# isoSPI-transceiver.net
KiCad netlist of a schematic drawn in Altium Designer
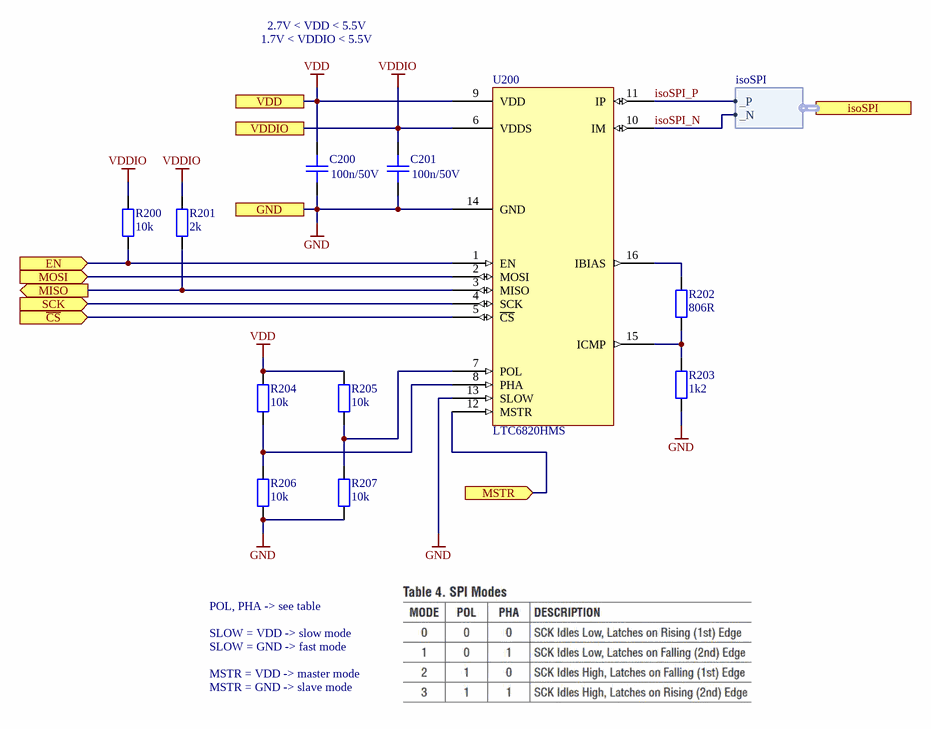
[diagram p0: isoSPI-transceiver.SchDoc]

(export (version "E")
  (design (tool "Eeschema 10.0.6"))
  (components
    (comp (ref "C200")
      (value "100n/50V")
      (footprint "CAPC1608X08N")
      (description "MLCC")
      (fields (field (name "PART NUMBER") "gen_C_ceramic_100n_50V_X7R_0603"))
      (libsource (lib "OE750") (part "C"))
    )
    (comp (ref "C201")
      (value "100n/50V")
      (footprint "CAPC1608X08N")
      (description "MLCC")
      (fields (field (name "PART NUMBER") "gen_C_ceramic_100n_50V_X7R_0603"))
      (libsource (lib "OE750") (part "C"))
    )
    (comp (ref "R200")
      (value "10k")
      (footprint "RESC1608X05N")
      (description "SMD Resistor 10k 0603")
      (fields (field (name "PART NUMBER") "gen_R_10k_0603") (field (name "TOLERANCE") "1%"))
      (libsource (lib "OE750") (part "R"))
    )
    (comp (ref "R201")
      (value "2k")
      (footprint "RESC1608X05N")
      (description "SMD Resistor 2k 0603")
      (fields (field (name "PART NUMBER") "gen_R_2k_0603") (field (name "TOLERANCE") "1%"))
      (libsource (lib "OE750") (part "R"))
    )
    (comp (ref "R202")
      (value "806R")
      (footprint "RESC1608X05N")
      (description "SMD Resistor 806R 0603")
      (fields (field (name "PART NUMBER") "gen_R_806R_0603") (field (name "TOLERANCE") "1%"))
      (libsource (lib "OE750") (part "R"))
    )
    (comp (ref "R203")
      (value "1k2")
      (footprint "RESC1608X05N")
      (description "SMD Resistor 1k2 0603")
      (fields (field (name "PART NUMBER") "gen_R_1k2_0603") (field (name "TOLERANCE") "1%"))
      (libsource (lib "OE750") (part "R"))
    )
    (comp (ref "R204")
      (value "10k")
      (footprint "RESC1608X05N")
      (description "SMD Resistor 10k 0603")
      (fields (field (name "PART NUMBER") "gen_R_10k_0603") (field (name "TOLERANCE") "1%"))
      (libsource (lib "OE750") (part "R"))
    )
    (comp (ref "R205")
      (value "10k")
      (footprint "RESC1608X05N")
      (description "SMD Resistor 10k 0603")
      (fields (field (name "PART NUMBER") "gen_R_10k_0603") (field (name "TOLERANCE") "1%"))
      (libsource (lib "OE750") (part "R"))
    )
    (comp (ref "R206")
      (value "10k")
      (footprint "RESC1608X05N")
      (description "SMD Resistor 10k 0603")
      (fields (field (name "PART NUMBER") "gen_R_10k_0603") (field (name "TOLERANCE") "1%"))
      (libsource (lib "OE750") (part "R"))
    )
    (comp (ref "R207")
      (value "10k")
      (footprint "RESC1608X05N")
      (description "SMD Resistor 10k 0603")
      (fields (field (name "PART NUMBER") "gen_R_10k_0603") (field (name "TOLERANCE") "1%"))
      (libsource (lib "OE750") (part "R"))
    )
    (comp (ref "U200")
      (value "LTC6820HMS")
      (footprint "LTC6820-MSOP")
      (description "isoSPI Isolated Communications Interface")
      (fields (field (name "MANUFACTURER") "Analog Devices"))
      (libsource (lib "OE750") (part "LTC6820"))
    )
  )
  (nets
    (net (code "2") (name "/CS") (class "Default")
      (node (ref "U200") (pin "5") (pinfunction "CS_5") (pintype "bidirectional"))
    )
    (net (code "3") (name "/EN") (class "Default")
      (node (ref "R200") (pin "1") (pinfunction "1_1") (pintype "passive"))
      (node (ref "U200") (pin "1") (pinfunction "EN_1") (pintype "input"))
    )
    (net (code "4") (name "/MISO") (class "Default")
      (node (ref "R201") (pin "1") (pinfunction "1_1") (pintype "passive"))
      (node (ref "U200") (pin "3") (pinfunction "MISO_3") (pintype "bidirectional"))
    )
    (net (code "5") (name "/MOSI") (class "Default")
      (node (ref "U200") (pin "2") (pinfunction "MOSI_2") (pintype "bidirectional"))
    )
    (net (code "6") (name "/MSTR") (class "Default")
      (node (ref "U200") (pin "12") (pinfunction "MSTR_12") (pintype "input"))
    )
    (net (code "7") (name "/SCK") (class "Default")
      (node (ref "U200") (pin "4") (pinfunction "SCK_4") (pintype "bidirectional"))
    )
    (net (code "8") (name "/isoSPI_N") (class "Default")
      (node (ref "U200") (pin "10") (pinfunction "IM_10") (pintype "bidirectional"))
    )
    (net (code "9") (name "/isoSPI_P") (class "Default")
      (node (ref "U200") (pin "11") (pinfunction "IP_11") (pintype "bidirectional"))
    )
    (net (code "11") (name "GND") (class "Default")
      (node (ref "C200") (pin "1") (pinfunction "1_1") (pintype "passive"))
      (node (ref "C201") (pin "1") (pinfunction "1_1") (pintype "passive"))
      (node (ref "R203") (pin "1") (pinfunction "1_1") (pintype "passive"))
      (node (ref "R206") (pin "1") (pinfunction "1_1") (pintype "passive"))
      (node (ref "R207") (pin "1") (pinfunction "1_1") (pintype "passive"))
      (node (ref "U200") (pin "13") (pinfunction "SLOW_13") (pintype "input"))
      (node (ref "U200") (pin "14") (pinfunction "GND_14") (pintype "power_in"))
    )
    (net (code "12") (name "Net-(U200-IBIAS)") (class "Default")
      (node (ref "R202") (pin "2") (pinfunction "2_2") (pintype "passive"))
      (node (ref "U200") (pin "16") (pinfunction "IBIAS_16") (pintype "output"))
    )
    (net (code "13") (name "Net-(U200-ICMP)") (class "Default")
      (node (ref "R202") (pin "1") (pinfunction "1_1") (pintype "passive"))
      (node (ref "R203") (pin "2") (pinfunction "2_2") (pintype "passive"))
      (node (ref "U200") (pin "15") (pinfunction "ICMP_15") (pintype "output"))
    )
    (net (code "14") (name "Net-(U200-PHA)") (class "Default")
      (node (ref "R204") (pin "1") (pinfunction "1_1") (pintype "passive"))
      (node (ref "R206") (pin "2") (pinfunction "2_2") (pintype "passive"))
      (node (ref "U200") (pin "8") (pinfunction "PHA_8") (pintype "input"))
    )
    (net (code "15") (name "Net-(U200-POL)") (class "Default")
      (node (ref "R205") (pin "1") (pinfunction "1_1") (pintype "passive"))
      (node (ref "R207") (pin "2") (pinfunction "2_2") (pintype "passive"))
      (node (ref "U200") (pin "7") (pinfunction "POL_7") (pintype "input"))
    )
    (net (code "16") (name "VDD") (class "Default")
      (node (ref "C200") (pin "2") (pinfunction "2_2") (pintype "passive"))
      (node (ref "R204") (pin "2") (pinfunction "2_2") (pintype "passive"))
      (node (ref "R205") (pin "2") (pinfunction "2_2") (pintype "passive"))
      (node (ref "U200") (pin "9") (pinfunction "VDD_9") (pintype "power_in"))
    )
    (net (code "17") (name "VDDIO") (class "Default")
      (node (ref "C201") (pin "2") (pinfunction "2_2") (pintype "passive"))
      (node (ref "R200") (pin "2") (pinfunction "2_2") (pintype "passive"))
      (node (ref "R201") (pin "2") (pinfunction "2_2") (pintype "passive"))
      (node (ref "U200") (pin "6") (pinfunction "VDDS_6") (pintype "power_in"))
    )
  )
)
